# COURONNE_PARTIE_I_SCHEMA.net
KiCad netlist of a schematic drawn in Altium Designer
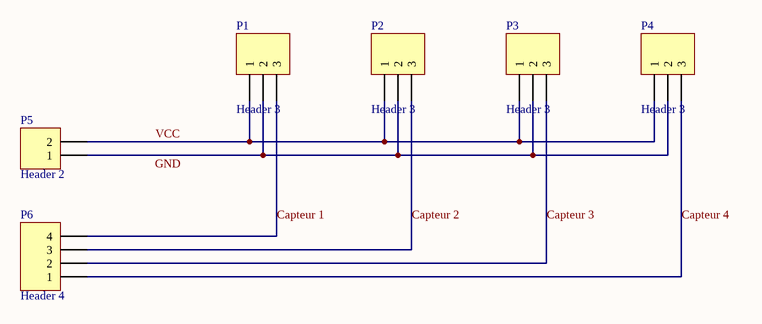
[diagram p0: COURONNE PARTIE I SCHEMA.SchDoc]

(export (version "E")
  (design (tool "Eeschema 10.0.6"))
  (components
    (comp (ref "P1")
      (value "Header 3")
      (footprint "HDR1X3")
      (description "Header, 3-Pin")
      (fields (field (name "PUBLISHER") "Altium Limited"))
      (libsource (lib "Miscellaneous Connectors") (part "Header 3"))
    )
    (comp (ref "P2")
      (value "Header 3")
      (footprint "HDR1X3")
      (description "Header, 3-Pin")
      (fields (field (name "PUBLISHER") "Altium Limited"))
      (libsource (lib "Miscellaneous Connectors") (part "Header 3"))
    )
    (comp (ref "P3")
      (value "Header 3")
      (footprint "HDR1X3")
      (description "Header, 3-Pin")
      (fields (field (name "PUBLISHER") "Altium Limited"))
      (libsource (lib "Miscellaneous Connectors") (part "Header 3"))
    )
    (comp (ref "P4")
      (value "Header 3")
      (footprint "HDR1X3")
      (description "Header, 3-Pin")
      (fields (field (name "PUBLISHER") "Altium Limited"))
      (libsource (lib "Miscellaneous Connectors") (part "Header 3"))
    )
    (comp (ref "P5")
      (value "Header 2")
      (footprint "HDR1X2")
      (description "Header, 2-Pin")
      (fields (field (name "PUBLISHER") "Altium Limited"))
      (libsource (lib "Miscellaneous Connectors") (part "Header 2"))
    )
    (comp (ref "P6")
      (value "Header 4")
      (footprint "HDR1X4")
      (description "Header, 4-Pin")
      (fields (field (name "PUBLISHER") "Altium Limited"))
      (libsource (lib "Miscellaneous Connectors") (part "Header 4"))
    )
  )
  (nets
    (net (code "1") (name "/Capteur 1") (class "Default")
      (node (ref "P1") (pin "3") (pinfunction "3_3") (pintype "passive"))
      (node (ref "P6") (pin "4") (pinfunction "4_4") (pintype "passive"))
    )
    (net (code "2") (name "/Capteur 2") (class "Default")
      (node (ref "P2") (pin "3") (pinfunction "3_3") (pintype "passive"))
      (node (ref "P6") (pin "3") (pinfunction "3_3") (pintype "passive"))
    )
    (net (code "3") (name "/Capteur 3") (class "Default")
      (node (ref "P3") (pin "3") (pinfunction "3_3") (pintype "passive"))
      (node (ref "P6") (pin "2") (pinfunction "2_2") (pintype "passive"))
    )
    (net (code "4") (name "/Capteur 4") (class "Default")
      (node (ref "P4") (pin "3") (pinfunction "3_3") (pintype "passive"))
      (node (ref "P6") (pin "1") (pinfunction "1_1") (pintype "passive"))
    )
    (net (code "5") (name "/GND") (class "Default")
      (node (ref "P1") (pin "2") (pinfunction "2_2") (pintype "passive"))
      (node (ref "P2") (pin "2") (pinfunction "2_2") (pintype "passive"))
      (node (ref "P3") (pin "2") (pinfunction "2_2") (pintype "passive"))
      (node (ref "P4") (pin "2") (pinfunction "2_2") (pintype "passive"))
      (node (ref "P5") (pin "1") (pinfunction "1_1") (pintype "passive"))
    )
    (net (code "6") (name "/VCC") (class "Default")
      (node (ref "P1") (pin "1") (pinfunction "1_1") (pintype "passive"))
      (node (ref "P2") (pin "1") (pinfunction "1_1") (pintype "passive"))
      (node (ref "P3") (pin "1") (pinfunction "1_1") (pintype "passive"))
      (node (ref "P4") (pin "1") (pinfunction "1_1") (pintype "passive"))
      (node (ref "P5") (pin "2") (pinfunction "2_2") (pintype "passive"))
    )
  )
)
